# USB_TTL.net
KiCad netlist of a schematic drawn in Altium Designer
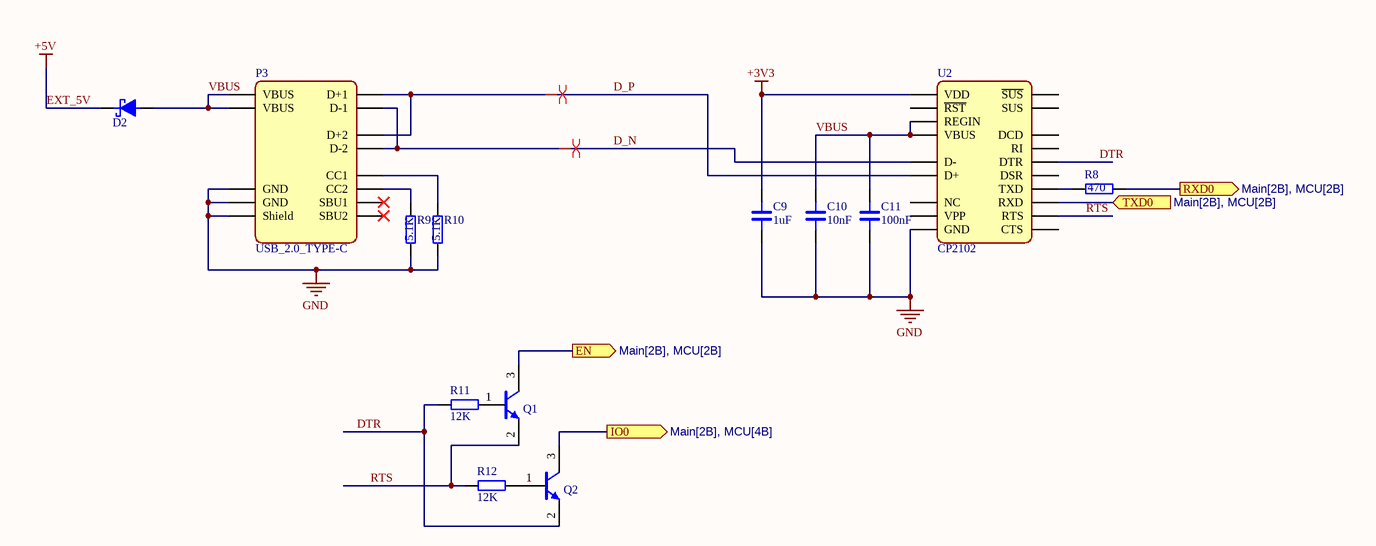
[diagram p0: USB_TTL.SchDoc]

(export (version "E")
  (design (tool "Eeschema 10.0.6"))
  (components
    (comp (ref "C9")
      (value "1uF")
      (footprint "CAP_0603")
      (description "0603 Multilayer Ceramic Capacitors MLCC - SMD/SMT ROHS")
      (fields (field (name "LCSC PART") "?"))
      (libsource (lib "FIC_OAL") (part "CAP_0603"))
    )
    (comp (ref "C10")
      (value "10nF")
      (footprint "CAP_0603")
      (description "0603 Multilayer Ceramic Capacitors MLCC - SMD/SMT ROHS")
      (fields (field (name "LCSC PART") "?"))
      (libsource (lib "FIC_OAL") (part "CAP_0603"))
    )
    (comp (ref "C11")
      (value "100nF")
      (footprint "CAP_0603")
      (description "0603 Multilayer Ceramic Capacitors MLCC - SMD/SMT ROHS")
      (fields (field (name "LCSC PART") "?"))
      (libsource (lib "FIC_OAL") (part "CAP_0603"))
    )
    (comp (ref "D2")
      (value "SS34")
      (footprint "DIO_SMA")
      (description "40V 500mV@3A 3A SMC (SBD)")
      (fields (field (name "MFR. PART") "?"))
      (libsource (lib "FIC_OAL") (part "DIO_SS34"))
    )
    (comp (ref "P3")
      (value "USB_2.0_TYPE-C")
      (footprint "CON_USB_2.0_TYPE-C")
      (description "USB Connectors USB Jack 2.0, Type-C, Horizontal SMT")
      (fields (field (name "MRF. PART") "?"))
      (libsource (lib "FIC_OAL") (part "CON_USB_2.0_TYPE-C"))
    )
    (comp (ref "Q1")
      (value "BC846x")
      (footprint "BJT_ BC846x")
      (description "Single Bipolar Transistor, NPN, 65 V, 100 mA, 250 mW, SOT23 (TO-236AB), 3 Pins, Surface Mount")
      (fields (field (name "MRF. PART") "?"))
      (libsource (lib "FIC_OAL") (part "BJT_ BC846x"))
    )
    (comp (ref "Q2")
      (value "BC846x")
      (footprint "BJT_ BC846x")
      (description "Single Bipolar Transistor, NPN, 65 V, 100 mA, 250 mW, SOT23 (TO-236AB), 3 Pins, Surface Mount")
      (fields (field (name "MRF. PART") "?"))
      (libsource (lib "FIC_OAL") (part "BJT_ BC846x"))
    )
    (comp (ref "R8")
      (value "470")
      (footprint "RES_0603")
      (description "0603 Thick Film Resistor - Surface Mount ROHS")
      (fields (field (name "MFR. PART") "?"))
      (libsource (lib "FIC_OAL") (part "RES_0603"))
    )
    (comp (ref "R9")
      (value "5.1K")
      (footprint "RES_0603")
      (description "0603 Thick Film Resistor - Surface Mount ROHS")
      (fields (field (name "MFR. PART") "?"))
      (libsource (lib "FIC_OAL") (part "RES_0603"))
    )
    (comp (ref "R10")
      (value "5.1K")
      (footprint "RES_0603")
      (description "0603 Thick Film Resistor - Surface Mount ROHS")
      (fields (field (name "MFR. PART") "?"))
      (libsource (lib "FIC_OAL") (part "RES_0603"))
    )
    (comp (ref "R11")
      (value "12K")
      (footprint "RES_0603")
      (description "0603 Thick Film Resistor - Surface Mount ROHS")
      (fields (field (name "MFR. PART") "?"))
      (libsource (lib "FIC_OAL") (part "RES_0603"))
    )
    (comp (ref "R12")
      (value "12K")
      (footprint "RES_0603")
      (description "0603 Thick Film Resistor - Surface Mount ROHS")
      (fields (field (name "MFR. PART") "?"))
      (libsource (lib "FIC_OAL") (part "RES_0603"))
    )
    (comp (ref "U2")
      (value "CP2102")
      (footprint "INF_CP2102")
      (description "USB to UART bridge USB 2.0 3.3V, CP2102-GMR, VFQFN-28")
      (fields (field (name "MRF. PART") "?"))
      (libsource (lib "FIC_OAL") (part "INF_CP2102"))
    )
  )
  (nets
    (net (code "1") (name "+3V3") (class "Default")
      (node (ref "C9") (pin "2") (pinfunction "2_2") (pintype "passive"))
      (node (ref "U2") (pin "6") (pinfunction "VDD_6") (pintype "passive"))
    )
    (net (code "2") (name "+5V") (class "Default")
      (node (ref "D2") (pin "C") (pinfunction "C_C") (pintype "passive"))
    )
    (net (code "3") (name "/DTR") (class "Default")
      (node (ref "Q2") (pin "2") (pinfunction "E_2") (pintype "passive"))
      (node (ref "R11") (pin "1") (pinfunction "1_1") (pintype "passive"))
      (node (ref "U2") (pin "28") (pinfunction "DTR_28") (pintype "passive"))
    )
    (net (code "4") (name "/D_N") (class "Default")
      (node (ref "P3") (pin "A7") (pinfunction "D-1_A7") (pintype "passive"))
      (node (ref "P3") (pin "B7") (pinfunction "D-2_B7") (pintype "passive"))
      (node (ref "U2") (pin "5") (pinfunction "D-_5") (pintype "passive"))
    )
    (net (code "5") (name "/D_P") (class "Default")
      (node (ref "P3") (pin "A6") (pinfunction "D+1_A6") (pintype "passive"))
      (node (ref "P3") (pin "B6") (pinfunction "D+2_B6") (pintype "passive"))
      (node (ref "U2") (pin "4") (pinfunction "D+_4") (pintype "passive"))
    )
    (net (code "6") (name "/EN") (class "Default")
      (node (ref "Q1") (pin "3") (pinfunction "C_3") (pintype "passive"))
    )
    (net (code "7") (name "/IO0") (class "Default")
      (node (ref "Q2") (pin "3") (pinfunction "C_3") (pintype "passive"))
    )
    (net (code "8") (name "/RTS") (class "Default")
      (node (ref "Q1") (pin "2") (pinfunction "E_2") (pintype "passive"))
      (node (ref "R12") (pin "1") (pinfunction "1_1") (pintype "passive"))
      (node (ref "U2") (pin "24") (pinfunction "RTS_24") (pintype "passive"))
    )
    (net (code "9") (name "/RXD0") (class "Default")
      (node (ref "R8") (pin "2") (pinfunction "2_2") (pintype "passive"))
    )
    (net (code "10") (name "/TXD0") (class "Default")
      (node (ref "U2") (pin "25") (pinfunction "RXD_25") (pintype "passive"))
    )
    (net (code "11") (name "/VBUS") (class "Default")
      (node (ref "C10") (pin "2") (pinfunction "2_2") (pintype "passive"))
      (node (ref "C11") (pin "2") (pinfunction "2_2") (pintype "passive"))
      (node (ref "D2") (pin "A") (pinfunction "A_A") (pintype "passive"))
      (node (ref "P3") (pin "A4/B9") (pinfunction "VBUS_A4/B9") (pintype "passive"))
      (node (ref "P3") (pin "A9/B4") (pinfunction "VBUS_A9/B4") (pintype "passive"))
      (node (ref "U2") (pin "7") (pinfunction "REGIN_7") (pintype "passive"))
      (node (ref "U2") (pin "8") (pinfunction "VBUS_8") (pintype "passive"))
    )
    (net (code "12") (name "GND") (class "Default")
      (node (ref "C10") (pin "1") (pinfunction "1_1") (pintype "passive"))
      (node (ref "C11") (pin "1") (pinfunction "1_1") (pintype "passive"))
      (node (ref "C9") (pin "1") (pinfunction "1_1") (pintype "passive"))
      (node (ref "P3") (pin "A1/B12") (pinfunction "GND_A1/B12") (pintype "passive"))
      (node (ref "P3") (pin "A12/B1") (pinfunction "GND_A12/B1") (pintype "passive"))
      (node (ref "P3") (pin "Shell") (pinfunction "Shield_Shell") (pintype "passive"))
      (node (ref "R10") (pin "1") (pinfunction "1_1") (pintype "passive"))
      (node (ref "R9") (pin "1") (pinfunction "1_1") (pintype "passive"))
      (node (ref "U2") (pin "3") (pinfunction "GND_3") (pintype "passive"))
    )
    (net (code "13") (name "Net-(P3-CC1)") (class "Default")
      (node (ref "P3") (pin "A5") (pinfunction "CC1_A5") (pintype "passive"))
      (node (ref "R10") (pin "2") (pinfunction "2_2") (pintype "passive"))
    )
    (net (code "14") (name "Net-(P3-CC2)") (class "Default")
      (node (ref "P3") (pin "B5") (pinfunction "CC2_B5") (pintype "passive"))
      (node (ref "R9") (pin "2") (pinfunction "2_2") (pintype "passive"))
    )
    (net (code "15") (name "Net-(Q1-B)") (class "Default")
      (node (ref "Q1") (pin "1") (pinfunction "B_1") (pintype "passive"))
      (node (ref "R11") (pin "2") (pinfunction "2_2") (pintype "passive"))
    )
    (net (code "16") (name "Net-(Q2-B)") (class "Default")
      (node (ref "Q2") (pin "1") (pinfunction "B_1") (pintype "passive"))
      (node (ref "R12") (pin "2") (pinfunction "2_2") (pintype "passive"))
    )
    (net (code "17") (name "Net-(U2-TXD)") (class "Default")
      (node (ref "R8") (pin "1") (pinfunction "1_1") (pintype "passive"))
      (node (ref "U2") (pin "26") (pinfunction "TXD_26") (pintype "passive"))
    )
    (net (code "18") (name "unconnected-(P3-SBU1-PadA8)") (class "Default")
      (node (ref "P3") (pin "A8") (pinfunction "SBU1_A8") (pintype "passive+no_connect"))
    )
    (net (code "19") (name "unconnected-(P3-SBU2-PadB8)") (class "Default")
      (node (ref "P3") (pin "B8") (pinfunction "SBU2_B8") (pintype "passive+no_connect"))
    )
    (net (code "20") (name "unconnected-(U2-CTS-Pad23)") (class "Default")
      (node (ref "U2") (pin "23") (pinfunction "CTS_23") (pintype "passive"))
    )
    (net (code "21") (name "unconnected-(U2-DCD-Pad1)") (class "Default")
      (node (ref "U2") (pin "1") (pinfunction "DCD_1") (pintype "passive"))
    )
    (net (code "22") (name "unconnected-(U2-DSR-Pad27)") (class "Default")
      (node (ref "U2") (pin "27") (pinfunction "DSR_27") (pintype "passive"))
    )
    (net (code "23") (name "unconnected-(U2-NC-Pad10)") (class "Default")
      (node (ref "U2") (pin "10") (pinfunction "NC_10") (pintype "passive"))
      (node (ref "U2") (pin "13") (pinfunction "NC_13") (pintype "passive"))
      (node (ref "U2") (pin "14") (pinfunction "NC_14") (pintype "passive"))
      (node (ref "U2") (pin "15") (pinfunction "NC_15") (pintype "passive"))
      (node (ref "U2") (pin "16") (pinfunction "NC_16") (pintype "passive"))
      (node (ref "U2") (pin "17") (pinfunction "NC_17") (pintype "passive"))
      (node (ref "U2") (pin "19") (pinfunction "NC_19") (pintype "passive"))
      (node (ref "U2") (pin "20") (pinfunction "NC_20") (pintype "passive"))
      (node (ref "U2") (pin "21") (pinfunction "NC_21") (pintype "passive"))
      (node (ref "U2") (pin "22") (pinfunction "NC_22") (pintype "passive"))
    )
    (net (code "24") (name "unconnected-(U2-RI-Pad2)") (class "Default")
      (node (ref "U2") (pin "2") (pinfunction "RI_2") (pintype "passive"))
    )
    (net (code "25") (name "unconnected-(U2-SUS-Pad12)") (class "Default")
      (node (ref "U2") (pin "12") (pinfunction "SUS_12") (pintype "passive"))
    )
    (net (code "26") (name "unconnected-(U2-VPP-Pad18)") (class "Default")
      (node (ref "U2") (pin "18") (pinfunction "VPP_18") (pintype "passive"))
    )
    (net (code "27") (name "unconnected-(U2-~{RST}-Pad9)") (class "Default")
      (node (ref "U2") (pin "9") (pinfunction "~{RST}_9") (pintype "passive"))
    )
    (net (code "28") (name "unconnected-(U2-~{SUS}-Pad11)") (class "Default")
      (node (ref "U2") (pin "11") (pinfunction "~{SUS}_11") (pintype "passive"))
    )
  )
)
